# Schematic_long_c.net
KiCad netlist of a schematic drawn in EasyEDA
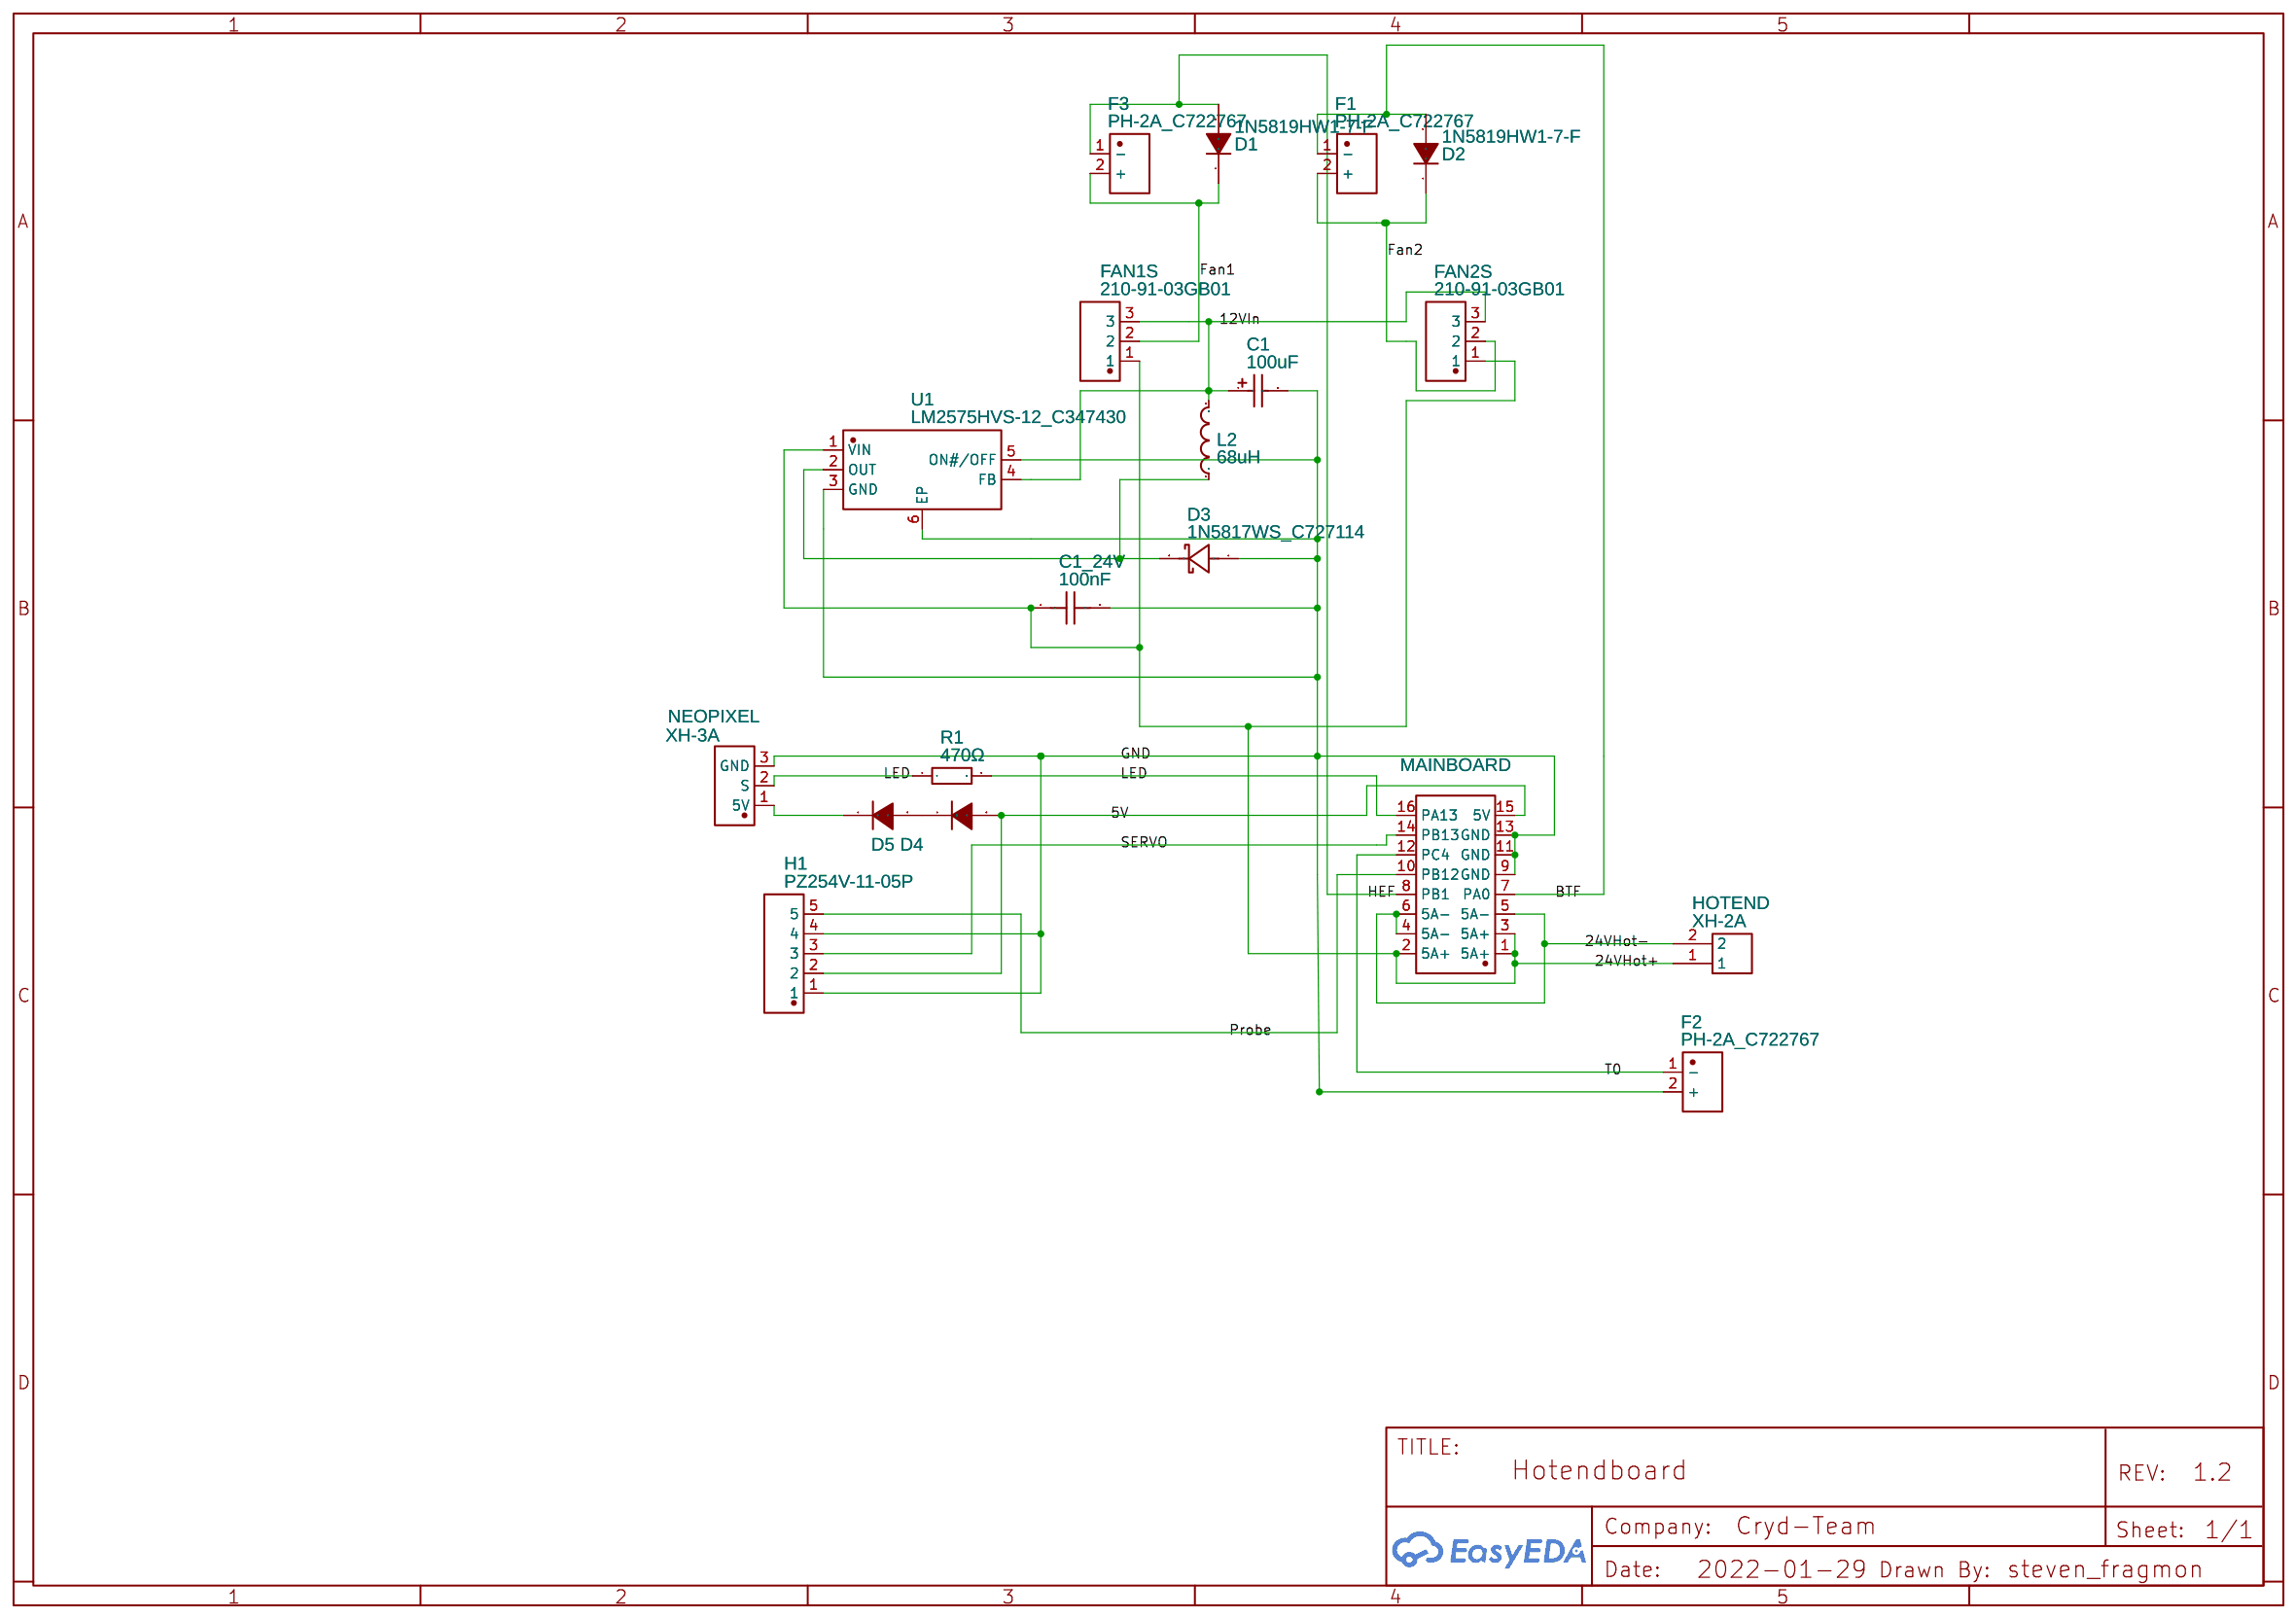
[diagram p0: schematic sheet]

(export (version "E")
  (design (tool "Eeschema 10.0.6"))
  (components
    (comp (ref "C1")
      (value "100uF")
      (fields
        (field (name "BOM_Manufacturer Part") "T491D107K016AT")
        (field (name "BOM_Supplier Part") "C110548")
      )
      (libsource (lib "") (part "T491D107K016AT"))
    )
    (comp (ref "C1_24V")
      (value "100nF")
      (fields
        (field (name "BOM_Manufacturer Part") "GRM188R71E104KA01D")
        (field (name "BOM_Supplier Part") "C77050")
      )
      (libsource (lib "") (part "GRM188R71E104KA01D"))
    )
    (comp (ref "D1")
      (value "1N5819HW1-7-F")
      (fields (field (name "BOM_Supplier Part") "C117948"))
      (libsource (lib "") (part "1N5819HW1-7-F"))
    )
    (comp (ref "D2")
      (value "1N5819HW1-7-F")
      (fields (field (name "BOM_Supplier Part") "C117948"))
      (libsource (lib "") (part "1N5819HW1-7-F"))
    )
    (comp (ref "D3")
      (value "1N5817WS_C727114")
      (fields (field (name "BOM_Manufacturer Part") "1N5817WS") (field (name "BOM_Supplier Part") "C727114"))
      (libsource (lib "") (part "1N5817WS_C727114"))
    )
    (comp (ref "D4")
      (value "1N4001F")
      (fields (field (name "BOM_Supplier Part") "C122841"))
      (libsource (lib "") (part "1N4001F"))
    )
    (comp (ref "D5")
      (value "1N4001F")
      (fields (field (name "BOM_Supplier Part") "C122841"))
      (libsource (lib "") (part "1N4001F"))
    )
    (comp (ref "F1")
      (value "PH-2A_C722767")
      (fields (field (name "BOM_Manufacturer Part") "PH-2A") (field (name "BOM_Supplier Part") "C722767"))
      (libsource (lib "") (part "PH-2A_C722767"))
    )
    (comp (ref "F2")
      (value "PH-2A_C722767")
      (fields (field (name "BOM_Manufacturer Part") "PH-2A") (field (name "BOM_Supplier Part") "C722767"))
      (libsource (lib "") (part "PH-2A_C722767"))
    )
    (comp (ref "F3")
      (value "PH-2A_C722767")
      (fields (field (name "BOM_Manufacturer Part") "PH-2A") (field (name "BOM_Supplier Part") "C722767"))
      (libsource (lib "") (part "PH-2A_C722767"))
    )
    (comp (ref "FAN1S")
      (value "210-91-03GB01")
      (fields (field (name "BOM_Supplier Part") "C390679"))
      (libsource (lib "") (part "210-91-03GB01_1"))
    )
    (comp (ref "FAN2S")
      (value "210-91-03GB01")
      (fields (field (name "BOM_Supplier Part") "C390679"))
      (libsource (lib "") (part "210-91-03GB01"))
    )
    (comp (ref "H1")
      (value "PZ254V-11-05P")
      (fields (field (name "BOM_Supplier Part") "C492404"))
      (libsource (lib "") (part "PZ254V-11-05P"))
    )
    (comp (ref "HOTEND")
      (value "XH-2A")
      (fields (field (name "BOM_Supplier Part") "C20079"))
      (libsource (lib "") (part "XH-2A"))
    )
    (comp (ref "L2")
      (value "68uH")
      (fields
        (field (name "BOM_Manufacturer Part") "SMNR4020-68UH")
        (field (name "BOM_Supplier Part") "C135265")
      )
      (libsource (lib "") (part "SMNR4020-68UH"))
    )
    (comp (ref "MAINBOARD")
      (value "IDC-CON-Angled-Latch-16P")
      (fields (field (name "BOM_Supplier Part") "C48023"))
      (libsource (lib "") (part "IDC-CON-Angled-Latch-16P"))
    )
    (comp (ref "NEOPIXEL")
      (value "XH-3A")
      (fields (field (name "BOM_Supplier Part") "C722863"))
      (libsource (lib "") (part "XH-3A_C722863"))
    )
    (comp (ref "R1")
      (value "470Ω")
      (fields
        (field (name "BOM_Manufacturer Part") "0603WAJ0471T5E")
        (field (name "BOM_Supplier Part") "C25241")
      )
      (libsource (lib "") (part "0603WAJ0471T5E"))
    )
    (comp (ref "U1")
      (value "LM2575HVS-12_C347430")
      (fields
        (field (name "BOM_Manufacturer Part") "LM2575HVS-12")
        (field (name "BOM_Supplier Part") "C347430")
      )
      (libsource (lib "") (part "LM2575HVS-12_C347430"))
    )
  )
  (nets
    (net (code "1") (name "/5V") (class "Default")
      (node (ref "D4") (pin "2") (pinfunction "A_2") (pintype "unspecified"))
      (node (ref "H1") (pin "2") (pinfunction "2_2") (pintype "unspecified"))
      (node (ref "MAINBOARD") (pin "15") (pinfunction "5V_15") (pintype "unspecified"))
    )
    (net (code "2") (name "/12VIn") (class "Default")
      (node (ref "C1") (pin "1") (pinfunction "1_1") (pintype "input"))
      (node (ref "FAN1S") (pin "3") (pinfunction "3_3") (pintype "unspecified"))
      (node (ref "FAN2S") (pin "3") (pinfunction "3_3") (pintype "unspecified"))
      (node (ref "L2") (pin "2") (pinfunction "2_2") (pintype "unspecified"))
      (node (ref "U1") (pin "4") (pinfunction "FB_4") (pintype "unspecified"))
    )
    (net (code "3") (name "/24VHot+") (class "Default")
      (node (ref "C1_24V") (pin "1") (pinfunction "1_1") (pintype "unspecified"))
      (node (ref "FAN1S") (pin "1") (pinfunction "1_1") (pintype "unspecified"))
      (node (ref "FAN2S") (pin "1") (pinfunction "1_1") (pintype "unspecified"))
      (node (ref "HOTEND") (pin "1") (pinfunction "1_1") (pintype "unspecified"))
      (node (ref "MAINBOARD") (pin "1") (pinfunction "5A+_1") (pintype "unspecified"))
      (node (ref "MAINBOARD") (pin "2") (pinfunction "5A+_2") (pintype "unspecified"))
      (node (ref "MAINBOARD") (pin "3") (pinfunction "5A+_3") (pintype "unspecified"))
      (node (ref "U1") (pin "1") (pinfunction "VIN_1") (pintype "unspecified"))
    )
    (net (code "4") (name "/24VHot-") (class "Default")
      (node (ref "HOTEND") (pin "2") (pinfunction "2_2") (pintype "unspecified"))
      (node (ref "MAINBOARD") (pin "4") (pinfunction "5A-_4") (pintype "unspecified"))
      (node (ref "MAINBOARD") (pin "5") (pinfunction "5A-_5") (pintype "unspecified"))
      (node (ref "MAINBOARD") (pin "6") (pinfunction "5A-_6") (pintype "unspecified"))
    )
    (net (code "5") (name "/BTF") (class "Default")
      (node (ref "D2") (pin "2") (pinfunction "A_2") (pintype "unspecified"))
      (node (ref "F1") (pin "1") (pinfunction "-_1") (pintype "unspecified"))
      (node (ref "MAINBOARD") (pin "7") (pinfunction "PA0_7") (pintype "unspecified"))
    )
    (net (code "6") (name "/Fan1") (class "Default")
      (node (ref "D1") (pin "1") (pinfunction "K_1") (pintype "unspecified"))
      (node (ref "F3") (pin "2") (pinfunction "+_2") (pintype "unspecified"))
      (node (ref "FAN1S") (pin "2") (pinfunction "2_2") (pintype "unspecified"))
    )
    (net (code "7") (name "/Fan2") (class "Default")
      (node (ref "D2") (pin "1") (pinfunction "K_1") (pintype "unspecified"))
      (node (ref "F1") (pin "2") (pinfunction "+_2") (pintype "unspecified"))
      (node (ref "FAN2S") (pin "2") (pinfunction "2_2") (pintype "unspecified"))
    )
    (net (code "8") (name "/GND") (class "Default")
      (node (ref "C1") (pin "2") (pinfunction "2_2") (pintype "input"))
      (node (ref "C1_24V") (pin "2") (pinfunction "2_2") (pintype "unspecified"))
      (node (ref "D3") (pin "1") (pinfunction "A_1") (pintype "unspecified"))
      (node (ref "F2") (pin "2") (pinfunction "+_2") (pintype "unspecified"))
      (node (ref "H1") (pin "1") (pinfunction "1_1") (pintype "unspecified"))
      (node (ref "H1") (pin "4") (pinfunction "4_4") (pintype "unspecified"))
      (node (ref "MAINBOARD") (pin "11") (pinfunction "GND_11") (pintype "unspecified"))
      (node (ref "MAINBOARD") (pin "13") (pinfunction "GND_13") (pintype "unspecified"))
      (node (ref "MAINBOARD") (pin "9") (pinfunction "GND_9") (pintype "unspecified"))
      (node (ref "NEOPIXEL") (pin "3") (pinfunction "GND_3") (pintype "unspecified"))
      (node (ref "U1") (pin "3") (pinfunction "GND_3") (pintype "unspecified"))
      (node (ref "U1") (pin "5") (pinfunction "ON#/OFF_5") (pintype "unspecified"))
      (node (ref "U1") (pin "6") (pinfunction "EP_6") (pintype "unspecified"))
    )
    (net (code "9") (name "/HEF") (class "Default")
      (node (ref "D1") (pin "2") (pinfunction "A_2") (pintype "unspecified"))
      (node (ref "F3") (pin "1") (pinfunction "-_1") (pintype "unspecified"))
      (node (ref "MAINBOARD") (pin "8") (pinfunction "PB1_8") (pintype "unspecified"))
    )
    (net (code "10") (name "/LED") (class "Default")
      (node (ref "MAINBOARD") (pin "16") (pinfunction "PA13_16") (pintype "unspecified"))
      (node (ref "NEOPIXEL") (pin "2") (pinfunction "S_2") (pintype "unspecified"))
      (node (ref "R1") (pin "1") (pinfunction "1_1") (pintype "input"))
      (node (ref "R1") (pin "2") (pinfunction "2_2") (pintype "input"))
    )
    (net (code "11") (name "/Probe") (class "Default")
      (node (ref "H1") (pin "5") (pinfunction "5_5") (pintype "unspecified"))
      (node (ref "MAINBOARD") (pin "10") (pinfunction "PB12_10") (pintype "unspecified"))
    )
    (net (code "12") (name "/SERVO") (class "Default")
      (node (ref "H1") (pin "3") (pinfunction "3_3") (pintype "unspecified"))
      (node (ref "MAINBOARD") (pin "14") (pinfunction "PB13_14") (pintype "unspecified"))
    )
    (net (code "13") (name "/T0") (class "Default")
      (node (ref "F2") (pin "1") (pinfunction "-_1") (pintype "unspecified"))
      (node (ref "MAINBOARD") (pin "12") (pinfunction "PC4_12") (pintype "unspecified"))
    )
    (net (code "14") (name "Net-(D3-K)") (class "Default")
      (node (ref "D3") (pin "2") (pinfunction "K_2") (pintype "unspecified"))
      (node (ref "L2") (pin "1") (pinfunction "1_1") (pintype "unspecified"))
      (node (ref "U1") (pin "2") (pinfunction "OUT_2") (pintype "unspecified"))
    )
    (net (code "15") (name "Net-(D4-C)") (class "Default")
      (node (ref "D4") (pin "1") (pinfunction "C_1") (pintype "unspecified"))
      (node (ref "D5") (pin "2") (pinfunction "A_2") (pintype "unspecified"))
    )
    (net (code "16") (name "Net-(D5-C)") (class "Default")
      (node (ref "D5") (pin "1") (pinfunction "C_1") (pintype "unspecified"))
      (node (ref "NEOPIXEL") (pin "1") (pinfunction "5V_1") (pintype "unspecified"))
    )
  )
)
